# ACPowerDistributionUSB-PD.net
KiCad netlist of a schematic drawn in Altium Designer
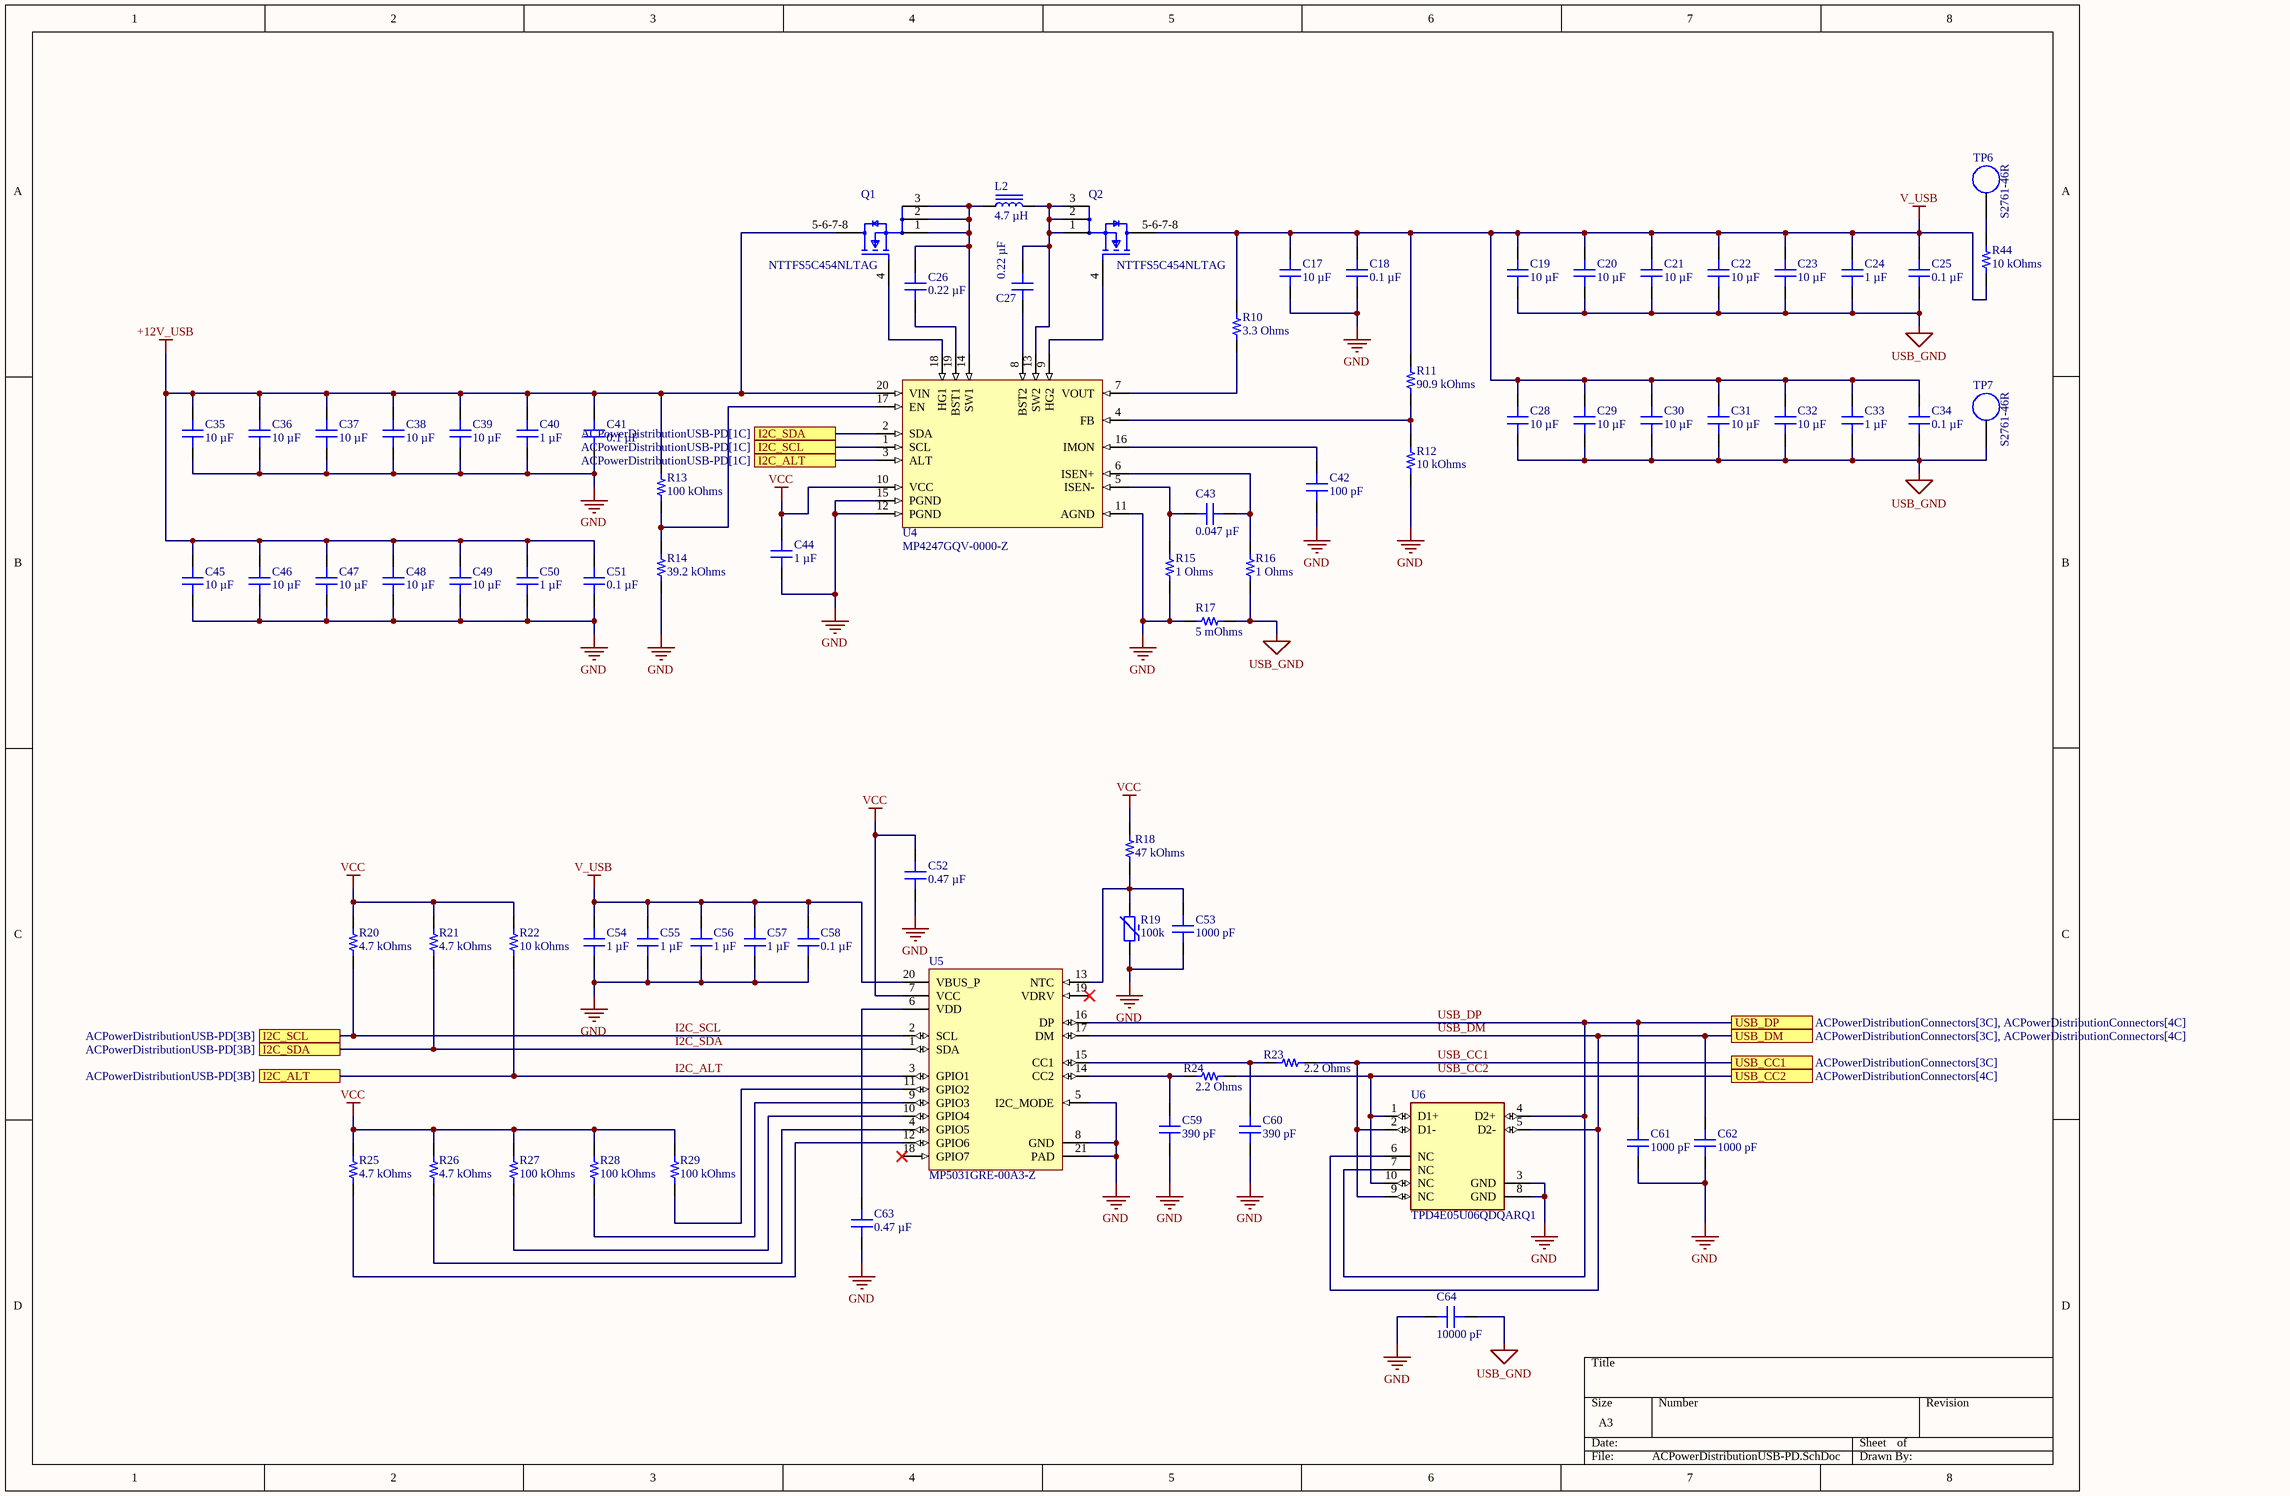
[diagram p0: ACPowerDistributionUSB-PD.SchDoc]

(export (version "E")
  (design (tool "Eeschema 10.0.6"))
  (components
    (comp (ref "C17")
      (value "10 µF")
      (footprint "CAP 1210_3225 - 1MM")
      (description "CAP CER 10UF 50V X7S 1210")
      (fields
        (field (name "PART NUMBER") "GCM32EC71H106KA03L")
        (field (name "MANUFACTURER") "Murata Electronics")
      )
      (libsource (lib "Celestial Altium Library - altium_library") (part "Capacitor"))
    )
    (comp (ref "C18")
      (value "0.1 µF")
      (footprint "CAP 0603_1608")
      (description "CAP CER 0.1UF 25V X7R 0603")
      (fields
        (field (name "PART NUMBER") "CL10B104KA8WPNC")
        (field (name "CAPACITANCE") "0.1 µF")
        (field (name "MANUFACTURER") "Samsung Electro-Mechanics")
      )
      (libsource (lib "Celestial Altium Library - altium_library") (part "Capacitor"))
    )
    (comp (ref "C19")
      (value "10 µF")
      (footprint "CAP 1210_3225 - 1MM")
      (description "CAP CER 10UF 50V X7S 1210")
      (fields
        (field (name "PART NUMBER") "GCM32EC71H106KA03L")
        (field (name "MANUFACTURER") "Murata Electronics")
      )
      (libsource (lib "Celestial Altium Library - altium_library") (part "Capacitor"))
    )
    (comp (ref "C20")
      (value "10 µF")
      (footprint "CAP 1210_3225 - 1MM")
      (description "CAP CER 10UF 50V X7S 1210")
      (fields
        (field (name "PART NUMBER") "GCM32EC71H106KA03L")
        (field (name "MANUFACTURER") "Murata Electronics")
      )
      (libsource (lib "Celestial Altium Library - altium_library") (part "Capacitor"))
    )
    (comp (ref "C21")
      (value "10 µF")
      (footprint "CAP 1210_3225 - 1MM")
      (description "CAP CER 10UF 50V X7S 1210")
      (fields
        (field (name "PART NUMBER") "GCM32EC71H106KA03L")
        (field (name "MANUFACTURER") "Murata Electronics")
      )
      (libsource (lib "Celestial Altium Library - altium_library") (part "Capacitor"))
    )
    (comp (ref "C22")
      (value "10 µF")
      (footprint "CAP 1210_3225 - 1MM")
      (description "CAP CER 10UF 50V X7S 1210")
      (fields
        (field (name "PART NUMBER") "GCM32EC71H106KA03L")
        (field (name "MANUFACTURER") "Murata Electronics")
      )
      (libsource (lib "Celestial Altium Library - altium_library") (part "Capacitor"))
    )
    (comp (ref "C23")
      (value "10 µF")
      (footprint "CAP 1210_3225 - 1MM")
      (description "CAP CER 10UF 50V X7S 1210")
      (fields
        (field (name "PART NUMBER") "GCM32EC71H106KA03L")
        (field (name "MANUFACTURER") "Murata Electronics")
      )
      (libsource (lib "Celestial Altium Library - altium_library") (part "Capacitor"))
    )
    (comp (ref "C24")
      (value "1 µF")
      (footprint "CAP 0603_1608")
      (description "CAP CER 1UF 25V X5R 0603")
      (fields
        (field (name "PART NUMBER") "CL10A105KA8NNNC")
        (field (name "CAPACITANCE") "1 µF")
        (field (name "MANUFACTURER") "Samsung Electro-Mechanics")
      )
      (libsource (lib "Celestial Altium Library - altium_library") (part "Capacitor"))
    )
    (comp (ref "C25")
      (value "0.1 µF")
      (footprint "CAP 0603_1608")
      (description "CAP CER 0.1UF 25V X7R 0603")
      (fields
        (field (name "PART NUMBER") "CL10B104KA8WPNC")
        (field (name "CAPACITANCE") "0.1 µF")
        (field (name "MANUFACTURER") "Samsung Electro-Mechanics")
      )
      (libsource (lib "Celestial Altium Library - altium_library") (part "Capacitor"))
    )
    (comp (ref "C26")
      (value "0.22 µF")
      (footprint "MURATA GRM188 0603_1608")
      (description "CAP CER 0.22UF 50V X7R 0603")
      (fields
        (field (name "PART NUMBER") "GRM188R71H224KAC4D")
        (field (name "CAPACITANCE") "0.22 µF")
        (field (name "MANUFACTURER") "Murata Electronics")
      )
      (libsource (lib "Celestial Altium Library - altium_library") (part "Capacitor"))
    )
    (comp (ref "C27")
      (value "0.22 µF")
      (footprint "MURATA GRM188 0603_1608")
      (description "CAP CER 0.22UF 50V X7R 0603")
      (fields
        (field (name "PART NUMBER") "GRM188R71H224KAC4D")
        (field (name "CAPACITANCE") "0.22 µF")
        (field (name "MANUFACTURER") "Murata Electronics")
      )
      (libsource (lib "Celestial Altium Library - altium_library") (part "Capacitor"))
    )
    (comp (ref "C28")
      (value "10 µF")
      (footprint "CAP 1210_3225 - 1MM")
      (description "CAP CER 10UF 50V X7S 1210")
      (fields
        (field (name "PART NUMBER") "GCM32EC71H106KA03L")
        (field (name "MANUFACTURER") "Murata Electronics")
      )
      (libsource (lib "Celestial Altium Library - altium_library") (part "Capacitor"))
    )
    (comp (ref "C29")
      (value "10 µF")
      (footprint "CAP 1210_3225 - 1MM")
      (description "CAP CER 10UF 50V X7S 1210")
      (fields
        (field (name "PART NUMBER") "GCM32EC71H106KA03L")
        (field (name "MANUFACTURER") "Murata Electronics")
      )
      (libsource (lib "Celestial Altium Library - altium_library") (part "Capacitor"))
    )
    (comp (ref "C30")
      (value "10 µF")
      (footprint "CAP 1210_3225 - 1MM")
      (description "CAP CER 10UF 50V X7S 1210")
      (fields
        (field (name "PART NUMBER") "GCM32EC71H106KA03L")
        (field (name "MANUFACTURER") "Murata Electronics")
      )
      (libsource (lib "Celestial Altium Library - altium_library") (part "Capacitor"))
    )
    (comp (ref "C31")
      (value "10 µF")
      (footprint "CAP 1210_3225 - 1MM")
      (description "CAP CER 10UF 50V X7S 1210")
      (fields
        (field (name "PART NUMBER") "GCM32EC71H106KA03L")
        (field (name "MANUFACTURER") "Murata Electronics")
      )
      (libsource (lib "Celestial Altium Library - altium_library") (part "Capacitor"))
    )
    (comp (ref "C32")
      (value "10 µF")
      (footprint "CAP 1210_3225 - 1MM")
      (description "CAP CER 10UF 50V X7S 1210")
      (fields
        (field (name "PART NUMBER") "GCM32EC71H106KA03L")
        (field (name "MANUFACTURER") "Murata Electronics")
      )
      (libsource (lib "Celestial Altium Library - altium_library") (part "Capacitor"))
    )
    (comp (ref "C33")
      (value "1 µF")
      (footprint "CAP 0603_1608")
      (description "CAP CER 1UF 25V X5R 0603")
      (fields
        (field (name "PART NUMBER") "CL10A105KA8NNNC")
        (field (name "CAPACITANCE") "1 µF")
        (field (name "MANUFACTURER") "Samsung Electro-Mechanics")
      )
      (libsource (lib "Celestial Altium Library - altium_library") (part "Capacitor"))
    )
    (comp (ref "C34")
      (value "0.1 µF")
      (footprint "CAP 0603_1608")
      (description "CAP CER 0.1UF 25V X7R 0603")
      (fields
        (field (name "PART NUMBER") "CL10B104KA8WPNC")
        (field (name "CAPACITANCE") "0.1 µF")
        (field (name "MANUFACTURER") "Samsung Electro-Mechanics")
      )
      (libsource (lib "Celestial Altium Library - altium_library") (part "Capacitor"))
    )
    (comp (ref "C35")
      (value "10 µF")
      (footprint "CAP 1210_3225 - 1MM")
      (description "CAP CER 10UF 50V X7S 1210")
      (fields
        (field (name "PART NUMBER") "GCM32EC71H106KA03L")
        (field (name "MANUFACTURER") "Murata Electronics")
      )
      (libsource (lib "Celestial Altium Library - altium_library") (part "Capacitor"))
    )
    (comp (ref "C36")
      (value "10 µF")
      (footprint "CAP 1210_3225 - 1MM")
      (description "CAP CER 10UF 50V X7S 1210")
      (fields
        (field (name "PART NUMBER") "GCM32EC71H106KA03L")
        (field (name "MANUFACTURER") "Murata Electronics")
      )
      (libsource (lib "Celestial Altium Library - altium_library") (part "Capacitor"))
    )
    (comp (ref "C37")
      (value "10 µF")
      (footprint "CAP 1210_3225 - 1MM")
      (description "CAP CER 10UF 50V X7S 1210")
      (fields
        (field (name "PART NUMBER") "GCM32EC71H106KA03L")
        (field (name "MANUFACTURER") "Murata Electronics")
      )
      (libsource (lib "Celestial Altium Library - altium_library") (part "Capacitor"))
    )
    (comp (ref "C38")
      (value "10 µF")
      (footprint "CAP 1210_3225 - 1MM")
      (description "CAP CER 10UF 50V X7S 1210")
      (fields
        (field (name "PART NUMBER") "GCM32EC71H106KA03L")
        (field (name "MANUFACTURER") "Murata Electronics")
      )
      (libsource (lib "Celestial Altium Library - altium_library") (part "Capacitor"))
    )
    (comp (ref "C39")
      (value "10 µF")
      (footprint "CAP 1210_3225 - 1MM")
      (description "CAP CER 10UF 50V X7S 1210")
      (fields
        (field (name "PART NUMBER") "GCM32EC71H106KA03L")
        (field (name "MANUFACTURER") "Murata Electronics")
      )
      (libsource (lib "Celestial Altium Library - altium_library") (part "Capacitor"))
    )
    (comp (ref "C40")
      (value "1 µF")
      (footprint "CAP 0603_1608")
      (description "CAP CER 1UF 25V X5R 0603")
      (fields
        (field (name "PART NUMBER") "CL10A105KA8NNNC")
        (field (name "CAPACITANCE") "1 µF")
        (field (name "MANUFACTURER") "Samsung Electro-Mechanics")
      )
      (libsource (lib "Celestial Altium Library - altium_library") (part "Capacitor"))
    )
    (comp (ref "C41")
      (value "0.1 µF")
      (footprint "CAP 0603_1608")
      (description "CAP CER 0.1UF 25V X7R 0603")
      (fields
        (field (name "PART NUMBER") "CL10B104KA8WPNC")
        (field (name "CAPACITANCE") "0.1 µF")
        (field (name "MANUFACTURER") "Samsung Electro-Mechanics")
      )
      (libsource (lib "Celestial Altium Library - altium_library") (part "Capacitor"))
    )
    (comp (ref "C42")
      (value "100 pF")
      (footprint "CAP 0603_1608")
      (description "CAP CER 100PF 25V C0G/NPO 0603")
      (fields
        (field (name "PART NUMBER") "CC0603JRNPO8BN101")
        (field (name "CAPACITANCE") "100 pF")
        (field (name "MANUFACTURER") "Yageo")
      )
      (libsource (lib "Celestial Altium Library - altium_library") (part "Capacitor"))
    )
    (comp (ref "C43")
      (value "0.047 µF")
      (footprint "CAP 0603_1608")
      (description "CAP CER 0.047UF 50V X7R 0603")
      (fields
        (field (name "PART NUMBER") "CL10B473KB8NNNC")
        (field (name "CAPACITANCE") "0.047 µF")
        (field (name "MANUFACTURER") "Samsung Electro-Mechanics")
      )
      (libsource (lib "Celestial Altium Library - altium_library") (part "Capacitor"))
    )
    (comp (ref "C44")
      (value "1 µF")
      (footprint "CAP 0603_1608")
      (description "CAP CER 1UF 25V X5R 0603")
      (fields
        (field (name "PART NUMBER") "CL10A105KA8NNNC")
        (field (name "CAPACITANCE") "1 µF")
        (field (name "MANUFACTURER") "Samsung Electro-Mechanics")
      )
      (libsource (lib "Celestial Altium Library - altium_library") (part "Capacitor"))
    )
    (comp (ref "C45")
      (value "10 µF")
      (footprint "CAP 1210_3225 - 1MM")
      (description "CAP CER 10UF 50V X7S 1210")
      (fields
        (field (name "PART NUMBER") "GCM32EC71H106KA03L")
        (field (name "MANUFACTURER") "Murata Electronics")
      )
      (libsource (lib "Celestial Altium Library - altium_library") (part "Capacitor"))
    )
    (comp (ref "C46")
      (value "10 µF")
      (footprint "CAP 1210_3225 - 1MM")
      (description "CAP CER 10UF 50V X7S 1210")
      (fields
        (field (name "PART NUMBER") "GCM32EC71H106KA03L")
        (field (name "MANUFACTURER") "Murata Electronics")
      )
      (libsource (lib "Celestial Altium Library - altium_library") (part "Capacitor"))
    )
    (comp (ref "C47")
      (value "10 µF")
      (footprint "CAP 1210_3225 - 1MM")
      (description "CAP CER 10UF 50V X7S 1210")
      (fields
        (field (name "PART NUMBER") "GCM32EC71H106KA03L")
        (field (name "MANUFACTURER") "Murata Electronics")
      )
      (libsource (lib "Celestial Altium Library - altium_library") (part "Capacitor"))
    )
    (comp (ref "C48")
      (value "10 µF")
      (footprint "CAP 1210_3225 - 1MM")
      (description "CAP CER 10UF 50V X7S 1210")
      (fields
        (field (name "PART NUMBER") "GCM32EC71H106KA03L")
        (field (name "MANUFACTURER") "Murata Electronics")
      )
      (libsource (lib "Celestial Altium Library - altium_library") (part "Capacitor"))
    )
    (comp (ref "C49")
      (value "10 µF")
      (footprint "CAP 1210_3225 - 1MM")
      (description "CAP CER 10UF 50V X7S 1210")
      (fields
        (field (name "PART NUMBER") "GCM32EC71H106KA03L")
        (field (name "MANUFACTURER") "Murata Electronics")
      )
      (libsource (lib "Celestial Altium Library - altium_library") (part "Capacitor"))
    )
    (comp (ref "C50")
      (value "1 µF")
      (footprint "CAP 0603_1608")
      (description "CAP CER 1UF 25V X5R 0603")
      (fields
        (field (name "PART NUMBER") "CL10A105KA8NNNC")
        (field (name "CAPACITANCE") "1 µF")
        (field (name "MANUFACTURER") "Samsung Electro-Mechanics")
      )
      (libsource (lib "Celestial Altium Library - altium_library") (part "Capacitor"))
    )
    (comp (ref "C51")
      (value "0.1 µF")
      (footprint "CAP 0603_1608")
      (description "CAP CER 0.1UF 25V X7R 0603")
      (fields
        (field (name "PART NUMBER") "CL10B104KA8WPNC")
        (field (name "CAPACITANCE") "0.1 µF")
        (field (name "MANUFACTURER") "Samsung Electro-Mechanics")
      )
      (libsource (lib "Celestial Altium Library - altium_library") (part "Capacitor"))
    )
    (comp (ref "C52")
      (value "0.47 µF")
      (footprint "CAP 0603_1608")
      (description "CAP CER 0.47UF 25V X5R 0603")
      (fields
        (field (name "PART NUMBER") "CC0603KRX5R8BB474")
        (field (name "CAPACITANCE") "0.47 µF")
        (field (name "MANUFACTURER") "Yageo")
      )
      (libsource (lib "Celestial Altium Library - altium_library") (part "Capacitor"))
    )
    (comp (ref "C53")
      (value "1000 pF")
      (footprint "CAP 0603_1608")
      (description "CAP CER 1000PF 16V C0G/NPO 0603")
      (fields
        (field (name "PART NUMBER") "CC0603JRNPO7BN102")
        (field (name "CAPACITANCE") "1000 pF")
        (field (name "MANUFACTURER") "Yageo")
      )
      (libsource (lib "Celestial Altium Library - altium_library") (part "Capacitor"))
    )
    (comp (ref "C54")
      (value "1 µF")
      (footprint "CAP 0603_1608")
      (description "CAP CER 1UF 25V X5R 0603")
      (fields
        (field (name "PART NUMBER") "CL10A105KA8NNNC")
        (field (name "CAPACITANCE") "1 µF")
        (field (name "MANUFACTURER") "Samsung Electro-Mechanics")
      )
      (libsource (lib "Celestial Altium Library - altium_library") (part "Capacitor"))
    )
    (comp (ref "C55")
      (value "1 µF")
      (footprint "CAP 0603_1608")
      (description "CAP CER 1UF 25V X5R 0603")
      (fields
        (field (name "PART NUMBER") "CL10A105KA8NNNC")
        (field (name "CAPACITANCE") "1 µF")
        (field (name "MANUFACTURER") "Samsung Electro-Mechanics")
      )
      (libsource (lib "Celestial Altium Library - altium_library") (part "Capacitor"))
    )
    (comp (ref "C56")
      (value "1 µF")
      (footprint "CAP 0603_1608")
      (description "CAP CER 1UF 25V X5R 0603")
      (fields
        (field (name "PART NUMBER") "CL10A105KA8NNNC")
        (field (name "CAPACITANCE") "1 µF")
        (field (name "MANUFACTURER") "Samsung Electro-Mechanics")
      )
      (libsource (lib "Celestial Altium Library - altium_library") (part "Capacitor"))
    )
    (comp (ref "C57")
      (value "1 µF")
      (footprint "CAP 0603_1608")
      (description "CAP CER 1UF 25V X5R 0603")
      (fields
        (field (name "PART NUMBER") "CL10A105KA8NNNC")
        (field (name "CAPACITANCE") "1 µF")
        (field (name "MANUFACTURER") "Samsung Electro-Mechanics")
      )
      (libsource (lib "Celestial Altium Library - altium_library") (part "Capacitor"))
    )
    (comp (ref "C58")
      (value "0.1 µF")
      (footprint "CAP 0603_1608")
      (description "CAP CER 0.1UF 25V X7R 0603")
      (fields
        (field (name "PART NUMBER") "CL10B104KA8WPNC")
        (field (name "CAPACITANCE") "0.1 µF")
        (field (name "MANUFACTURER") "Samsung Electro-Mechanics")
      )
      (libsource (lib "Celestial Altium Library - altium_library") (part "Capacitor"))
    )
    (comp (ref "C59")
      (value "390 pF")
      (footprint "CAP 0603_1608")
      (description "CAP CER 390PF 50V X7R 0603")
      (fields
        (field (name "PART NUMBER") "CC0603KRX7R9BB391")
        (field (name "CAPACITANCE") "390 pF")
        (field (name "MANUFACTURER") "Yageo")
      )
      (libsource (lib "Celestial Altium Library - altium_library") (part "Capacitor"))
    )
    (comp (ref "C60")
      (value "390 pF")
      (footprint "CAP 0603_1608")
      (description "CAP CER 390PF 50V X7R 0603")
      (fields
        (field (name "PART NUMBER") "CC0603KRX7R9BB391")
        (field (name "CAPACITANCE") "390 pF")
        (field (name "MANUFACTURER") "Yageo")
      )
      (libsource (lib "Celestial Altium Library - altium_library") (part "Capacitor"))
    )
    (comp (ref "C61")
      (value "1000 pF")
      (footprint "CAP 0603_1608")
      (description "CAP CER 1000PF 50V X8R 0603")
      (fields
        (field (name "PART NUMBER") "C1608X8R1H102K080AA")
        (field (name "CAPACITANCE") "1000 pF")
        (field (name "MANUFACTURER") "TDK Corporation")
      )
      (libsource (lib "Celestial Altium Library - altium_library") (part "Capacitor"))
    )
    (comp (ref "C62")
      (value "1000 pF")
      (footprint "CAP 0603_1608")
      (description "CAP CER 1000PF 50V X8R 0603")
      (fields
        (field (name "PART NUMBER") "C1608X8R1H102K080AA")
        (field (name "CAPACITANCE") "1000 pF")
        (field (name "MANUFACTURER") "TDK Corporation")
      )
      (libsource (lib "Celestial Altium Library - altium_library") (part "Capacitor"))
    )
    (comp (ref "C63")
      (value "0.47 µF")
      (footprint "CAP 0603_1608")
      (description "CAP CER 0.47UF 25V X5R 0603")
      (fields
        (field (name "PART NUMBER") "CC0603KRX5R8BB474")
        (field (name "CAPACITANCE") "0.47 µF")
        (field (name "MANUFACTURER") "Yageo")
      )
      (libsource (lib "Celestial Altium Library - altium_library") (part "Capacitor"))
    )
    (comp (ref "C64")
      (value "10000 pF")
      (footprint "CAP 0603_1608")
      (description "CAP CER 10000PF 50V X8R 0603")
      (fields
        (field (name "PART NUMBER") "CGA3E2X8R1H103K080AA")
        (field (name "CAPACITANCE") "10000 pF")
        (field (name "MANUFACTURER") "TDK Corporation")
      )
      (libsource (lib "Celestial Altium Library - altium_library") (part "Capacitor"))
    )
    (comp (ref "L2")
      (value "4.7 µH")
      (footprint "WURTH WE-HCI 7040")
      (description "FIXED IND 4.7UH 6A 19.5 MOHM SMD")
      (fields (field (name "PART NUMBER") "744311470") (field (name "MANUFACTURER") "Würth Elektronik"))
      (libsource (lib "Celestial Altium Library - altium_library") (part "Inductor"))
    )
    (comp (ref "Q1")
      (value "NTTFS5C454NLTAG")
      (footprint "FP-511AB-MFG")
      (libsource (lib "Altium Content Vault") (part "7382af88e928fdc71488234cfaaf11c"))
    )
    (comp (ref "Q2")
      (value "NTTFS5C454NLTAG")
      (footprint "FP-511AB-MFG")
      (libsource (lib "Altium Content Vault") (part "7382af88e928fdc71488234cfaaf11c"))
    )
    (comp (ref "R10")
      (value "3.3 Ohms")
      (footprint "RES 0603_1608")
      (description "RES 3.3 OHM 1% 1/10W 0603")
      (fields
        (field (name "PART NUMBER") "RMCF0603FT3R30")
        (field (name "MANUFACTURER") "Stackpole Electronics Inc")
      )
      (libsource (lib "Celestial Altium Library - altium_library") (part "Resistor"))
    )
    (comp (ref "R11")
      (value "90.9 kOhms")
      (footprint "RES 0603_1608")
      (description "RES 90.9K OHM 1% 1/10W 0603")
      (fields
        (field (name "PART NUMBER") "RMCF0603FT90K9")
        (field (name "MANUFACTURER") "Stackpole Electronics Inc")
      )
      (libsource (lib "Celestial Altium Library - altium_library") (part "Resistor"))
    )
    (comp (ref "R12")
      (value "10 kOhms")
      (footprint "RES 0603_1608")
      (description "RES 10K OHM 1% 1/10W 0603")
      (fields
        (field (name "PART NUMBER") "RMCF0603FT10K0")
        (field (name "MANUFACTURER") "Stackpole Electronics Inc")
      )
      (libsource (lib "Celestial Altium Library - altium_library") (part "Resistor"))
    )
    (comp (ref "R13")
      (value "100 kOhms")
      (footprint "RES 0603_1608")
      (description "RES 100K OHM 1% 1/10W 0603")
      (fields
        (field (name "PART NUMBER") "RMCF0603FT100K")
        (field (name "MANUFACTURER") "Stackpole Electronics Inc")
      )
      (libsource (lib "Celestial Altium Library - altium_library") (part "Resistor"))
    )
    (comp (ref "R14")
      (value "39.2 kOhms")
      (footprint "RES 0603_1608")
      (description "RES 39.2K OHM 1% 1/10W 0603")
      (fields
        (field (name "PART NUMBER") "RMCF0603FT39K2")
        (field (name "MANUFACTURER") "Stackpole Electronics Inc")
      )
      (libsource (lib "Celestial Altium Library - altium_library") (part "Resistor"))
    )
    (comp (ref "R15")
      (value "1 Ohms")
      (footprint "RES 0603_1608")
      (description "RES 1 OHM 1% 1/10W 0603")
      (fields
        (field (name "PART NUMBER") "RMCF0603FT1R00")
        (field (name "MANUFACTURER") "Stackpole Electronics Inc")
      )
      (libsource (lib "Celestial Altium Library - altium_library") (part "Resistor"))
    )
    (comp (ref "R16")
      (value "1 Ohms")
      (footprint "RES 0603_1608")
      (description "RES 1 OHM 1% 1/10W 0603")
      (fields
        (field (name "PART NUMBER") "RMCF0603FT1R00")
        (field (name "MANUFACTURER") "Stackpole Electronics Inc")
      )
      (libsource (lib "Celestial Altium Library - altium_library") (part "Resistor"))
    )
    (comp (ref "R17")
      (value "5 mOhms")
      (footprint "STACKPOLE CSR1206")
      (description "RES 0.005 OHM 1% 1W 1206")
      (fields (field (name "PART NUMBER") "CFN1206AFX-R005ELF") (field (name "MANUFACTURER") "Bourns Inc."))
      (libsource (lib "Celestial Altium Library - altium_library") (part "Resistor"))
    )
    (comp (ref "R18")
      (value "47 kOhms")
      (footprint "RES 0603_1608")
      (description "RES 47K OHM 1% 1/10W 0603")
      (fields
        (field (name "PART NUMBER") "RMCF0603FT47K0")
        (field (name "MANUFACTURER") "Stackpole Electronics Inc")
      )
      (libsource (lib "Celestial Altium Library - altium_library") (part "Resistor"))
    )
    (comp (ref "R19")
      (value "100k")
      (footprint "NTC 0603_1608")
      (description "THERM NTC 100KOHM 4200K 0603")
      (fields (field (name "PART NUMBER") "B57355V5104F360") (field (name "MANUFACTURER") "EPCOS (TDK)"))
      (libsource (lib "Celestial Altium Library - altium_library") (part "Thermistor"))
    )
    (comp (ref "R20")
      (value "4.7 kOhms")
      (footprint "RES 0603_1608")
      (description "RES 4.7K OHM 1% 1/10W 0603")
      (fields
        (field (name "PART NUMBER") "RMCF0603FT4K70")
        (field (name "MANUFACTURER") "Stackpole Electronics Inc")
      )
      (libsource (lib "Celestial Altium Library - altium_library") (part "Resistor"))
    )
    (comp (ref "R21")
      (value "4.7 kOhms")
      (footprint "RES 0603_1608")
      (description "RES 4.7K OHM 1% 1/10W 0603")
      (fields
        (field (name "PART NUMBER") "RMCF0603FT4K70")
        (field (name "MANUFACTURER") "Stackpole Electronics Inc")
      )
      (libsource (lib "Celestial Altium Library - altium_library") (part "Resistor"))
    )
    (comp (ref "R22")
      (value "10 kOhms")
      (footprint "RES 0603_1608")
      (description "RES 10K OHM 1% 1/10W 0603")
      (fields
        (field (name "PART NUMBER") "RMCF0603FT10K0")
        (field (name "MANUFACTURER") "Stackpole Electronics Inc")
      )
      (libsource (lib "Celestial Altium Library - altium_library") (part "Resistor"))
    )
    (comp (ref "R23")
      (value "2.2 Ohms")
      (footprint "RES 0603_1608")
      (description "RES 2.2 OHM 1% 1/10W 0603")
      (fields
        (field (name "PART NUMBER") "RMCF0603FT2R20")
        (field (name "MANUFACTURER") "Stackpole Electronics Inc")
      )
      (libsource (lib "Celestial Altium Library - altium_library") (part "Resistor"))
    )
    (comp (ref "R24")
      (value "2.2 Ohms")
      (footprint "RES 0603_1608")
      (description "RES 2.2 OHM 1% 1/10W 0603")
      (fields
        (field (name "PART NUMBER") "RMCF0603FT2R20")
        (field (name "MANUFACTURER") "Stackpole Electronics Inc")
      )
      (libsource (lib "Celestial Altium Library - altium_library") (part "Resistor"))
    )
    (comp (ref "R25")
      (value "4.7 kOhms")
      (footprint "RES 0603_1608")
      (description "RES 4.7K OHM 1% 1/10W 0603")
      (fields
        (field (name "PART NUMBER") "RMCF0603FT4K70")
        (field (name "MANUFACTURER") "Stackpole Electronics Inc")
      )
      (libsource (lib "Celestial Altium Library - altium_library") (part "Resistor"))
    )
    (comp (ref "R26")
      (value "4.7 kOhms")
      (footprint "RES 0603_1608")
      (description "RES 4.7K OHM 1% 1/10W 0603")
      (fields
        (field (name "PART NUMBER") "RMCF0603FT4K70")
        (field (name "MANUFACTURER") "Stackpole Electronics Inc")
      )
      (libsource (lib "Celestial Altium Library - altium_library") (part "Resistor"))
    )
    (comp (ref "R27")
      (value "100 kOhms")
      (footprint "RES 0603_1608")
      (description "RES 100K OHM 1% 1/10W 0603")
      (fields
        (field (name "PART NUMBER") "RMCF0603FT100K")
        (field (name "MANUFACTURER") "Stackpole Electronics Inc")
      )
      (libsource (lib "Celestial Altium Library - altium_library") (part "Resistor"))
    )
    (comp (ref "R28")
      (value "100 kOhms")
      (footprint "RES 0603_1608")
      (description "RES 100K OHM 1% 1/10W 0603")
      (fields
        (field (name "PART NUMBER") "RMCF0603FT100K")
        (field (name "MANUFACTURER") "Stackpole Electronics Inc")
      )
      (libsource (lib "Celestial Altium Library - altium_library") (part "Resistor"))
    )
    (comp (ref "R29")
      (value "100 kOhms")
      (footprint "RES 0603_1608")
      (description "RES 100K OHM 1% 1/10W 0603")
      (fields
        (field (name "PART NUMBER") "RMCF0603FT100K")
        (field (name "MANUFACTURER") "Stackpole Electronics Inc")
      )
      (libsource (lib "Celestial Altium Library - altium_library") (part "Resistor"))
    )
    (comp (ref "R44")
      (value "10 kOhms")
      (footprint "RES 0603_1608")
      (description "RES 10K OHM 1% 1/10W 0603")
      (fields
        (field (name "PART NUMBER") "RMCF0603FT10K0")
        (field (name "MANUFACTURER") "Stackpole Electronics Inc")
      )
      (libsource (lib "Celestial Altium Library - altium_library") (part "Resistor"))
    )
    (comp (ref "TP6")
      (value "S2761-46R")
      (footprint "S2761-46R")
      (libsource (lib "PersonalLibrary") (part "S2761-46R"))
    )
    (comp (ref "TP7")
      (value "S2761-46R")
      (footprint "S2761-46R")
      (libsource (lib "PersonalLibrary") (part "S2761-46R"))
    )
    (comp (ref "U4")
      (value "MP4247GQV-0000-Z")
      (footprint "MP4247GQV")
      (libsource (lib "PersonalLibrary") (part "MP4247GQV-0000-Z"))
    )
    (comp (ref "U5")
      (value "MP5031GRE-00A3-Z")
      (footprint "MP5031GRE")
      (libsource (lib "PersonalLibrary") (part "MP5031GRE-00A3-Z"))
    )
    (comp (ref "U6")
      (value "TPD4E05U06QDQARQ1")
      (footprint "FP-DQA0010A-MFG")
      (description "TVS DIODE 5.5V 14V 10USON")
      (fields
        (field (name "OCTOPART") "https://octopart.com/tpd4e05u06qdqarq1-texas+instruments-48523459")
        (field (name "MANUFACTURER") "Texas Instruments")
      )
      (libsource (lib "Altium Content Vault") (part "f11f7ff102fa2b028e1355c732c836d"))
    )
  )
  (nets
    (net (code "1") (name "+12V_USB") (class "Default")
      (node (ref "C35") (pin "2") (pinfunction "2_2") (pintype "passive"))
      (node (ref "C36") (pin "2") (pinfunction "2_2") (pintype "passive"))
      (node (ref "C37") (pin "2") (pinfunction "2_2") (pintype "passive"))
      (node (ref "C38") (pin "2") (pinfunction "2_2") (pintype "passive"))
      (node (ref "C39") (pin "2") (pinfunction "2_2") (pintype "passive"))
      (node (ref "C40") (pin "2") (pinfunction "2_2") (pintype "passive"))
      (node (ref "C41") (pin "2") (pinfunction "2_2") (pintype "passive"))
      (node (ref "C45") (pin "2") (pinfunction "2_2") (pintype "passive"))
      (node (ref "C46") (pin "2") (pinfunction "2_2") (pintype "passive"))
      (node (ref "C47") (pin "2") (pinfunction "2_2") (pintype "passive"))
      (node (ref "C48") (pin "2") (pinfunction "2_2") (pintype "passive"))
      (node (ref "C49") (pin "2") (pinfunction "2_2") (pintype "passive"))
      (node (ref "C50") (pin "2") (pinfunction "2_2") (pintype "passive"))
      (node (ref "C51") (pin "2") (pinfunction "2_2") (pintype "passive"))
      (node (ref "Q1") (pin "5-6-7-8") (pinfunction "D_5-6-7-8") (pintype "passive"))
      (node (ref "R13") (pin "2") (pinfunction "2_2") (pintype "passive"))
      (node (ref "U4") (pin "20") (pinfunction "VIN_20") (pintype "input"))
    )
    (net (code "2") (name "/I2C_ALT") (class "Default")
      (node (ref "R22") (pin "1") (pinfunction "1_1") (pintype "passive"))
      (node (ref "U4") (pin "3") (pinfunction "ALT_3") (pintype "input"))
      (node (ref "U5") (pin "3") (pinfunction "GPIO1_3") (pintype "bidirectional"))
    )
    (net (code "3") (name "/I2C_SCL") (class "Default")
      (node (ref "R20") (pin "1") (pinfunction "1_1") (pintype "passive"))
      (node (ref "U4") (pin "1") (pinfunction "SCL_1") (pintype "input"))
      (node (ref "U5") (pin "2") (pinfunction "SCL_2") (pintype "bidirectional"))
    )
    (net (code "4") (name "/I2C_SDA") (class "Default")
      (node (ref "R21") (pin "1") (pinfunction "1_1") (pintype "passive"))
      (node (ref "U4") (pin "2") (pinfunction "SDA_2") (pintype "input"))
      (node (ref "U5") (pin "1") (pinfunction "SDA_1") (pintype "bidirectional"))
    )
    (net (code "5") (name "/USB_CC1") (class "Default")
      (node (ref "R23") (pin "2") (pinfunction "2_2") (pintype "passive"))
      (node (ref "U6") (pin "2") (pinfunction "D1-_2") (pintype "bidirectional"))
      (node (ref "U6") (pin "9") (pinfunction "NC_9") (pintype "bidirectional"))
    )
    (net (code "6") (name "/USB_CC2") (class "Default")
      (node (ref "R24") (pin "2") (pinfunction "2_2") (pintype "passive"))
      (node (ref "U6") (pin "1") (pinfunction "D1+_1") (pintype "bidirectional"))
      (node (ref "U6") (pin "10") (pinfunction "NC_10") (pintype "bidirectional"))
    )
    (net (code "7") (name "/USB_DM") (class "Default")
      (node (ref "C62") (pin "2") (pinfunction "2_2") (pintype "passive"))
      (node (ref "U5") (pin "17") (pinfunction "DM_17") (pintype "bidirectional"))
      (node (ref "U6") (pin "5") (pinfunction "D2-_5") (pintype "bidirectional"))
      (node (ref "U6") (pin "6") (pinfunction "NC_6") (pintype "passive"))
    )
    (net (code "8") (name "/USB_DP") (class "Default")
      (node (ref "C61") (pin "2") (pinfunction "2_2") (pintype "passive"))
      (node (ref "U5") (pin "16") (pinfunction "DP_16") (pintype "bidirectional"))
      (node (ref "U6") (pin "4") (pinfunction "D2+_4") (pintype "bidirectional"))
      (node (ref "U6") (pin "7") (pinfunction "NC_7") (pintype "passive"))
    )
    (net (code "9") (name "GND") (class "Default")
      (node (ref "C17") (pin "1") (pinfunction "1_1") (pintype "passive"))
      (node (ref "C18") (pin "1") (pinfunction "1_1") (pintype "passive"))
      (node (ref "C35") (pin "1") (pinfunction "1_1") (pintype "passive"))
      (node (ref "C36") (pin "1") (pinfunction "1_1") (pintype "passive"))
      (node (ref "C37") (pin "1") (pinfunction "1_1") (pintype "passive"))
      (node (ref "C38") (pin "1") (pinfunction "1_1") (pintype "passive"))
      (node (ref "C39") (pin "1") (pinfunction "1_1") (pintype "passive"))
      (node (ref "C40") (pin "1") (pinfunction "1_1") (pintype "passive"))
      (node (ref "C41") (pin "1") (pinfunction "1_1") (pintype "passive"))
      (node (ref "C42") (pin "1") (pinfunction "1_1") (pintype "passive"))
      (node (ref "C44") (pin "1") (pinfunction "1_1") (pintype "passive"))
      (node (ref "C45") (pin "1") (pinfunction "1_1") (pintype "passive"))
      (node (ref "C46") (pin "1") (pinfunction "1_1") (pintype "passive"))
      (node (ref "C47") (pin "1") (pinfunction "1_1") (pintype "passive"))
      (node (ref "C48") (pin "1") (pinfunction "1_1") (pintype "passive"))
      (node (ref "C49") (pin "1") (pinfunction "1_1") (pintype "passive"))
      (node (ref "C50") (pin "1") (pinfunction "1_1") (pintype "passive"))
      (node (ref "C51") (pin "1") (pinfunction "1_1") (pintype "passive"))
      (node (ref "C52") (pin "1") (pinfunction "1_1") (pintype "passive"))
      (node (ref "C53") (pin "1") (pinfunction "1_1") (pintype "passive"))
      (node (ref "C54") (pin "1") (pinfunction "1_1") (pintype "passive"))
      (node (ref "C55") (pin "1") (pinfunction "1_1") (pintype "passive"))
      (node (ref "C56") (pin "1") (pinfunction "1_1") (pintype "passive"))
      (node (ref "C57") (pin "1") (pinfunction "1_1") (pintype "passive"))
      (node (ref "C58") (pin "1") (pinfunction "1_1") (pintype "passive"))
      (node (ref "C59") (pin "1") (pinfunction "1_1") (pintype "passive"))
      (node (ref "C60") (pin "1") (pinfunction "1_1") (pintype "passive"))
      (node (ref "C61") (pin "1") (pinfunction "1_1") (pintype "passive"))
      (node (ref "C62") (pin "1") (pinfunction "1_1") (pintype "passive"))
      (node (ref "C63") (pin "1") (pinfunction "1_1") (pintype "passive"))
      (node (ref "C64") (pin "1") (pinfunction "1_1") (pintype "passive"))
      (node (ref "R12") (pin "1") (pinfunction "1_1") (pintype "passive"))
      (node (ref "R14") (pin "1") (pinfunction "1_1") (pintype "passive"))
      (node (ref "R15") (pin "1") (pinfunction "1_1") (pintype "passive"))
      (node (ref "R17") (pin "1") (pinfunction "1_1") (pintype "passive"))
      (node (ref "R19") (pin "1") (pinfunction "1_1") (pintype "passive"))
      (node (ref "U4") (pin "11") (pinfunction "AGND_11") (pintype "input"))
      (node (ref "U4") (pin "12") (pinfunction "PGND_12") (pintype "input"))
      (node (ref "U4") (pin "15") (pinfunction "PGND_15") (pintype "input"))
      (node (ref "U5") (pin "21") (pinfunction "PAD_21") (pintype "power_in"))
      (node (ref "U5") (pin "5") (pinfunction "I2C_MODE_5") (pintype "input"))
      (node (ref "U5") (pin "8") (pinfunction "GND_8") (pintype "power_in"))
      (node (ref "U6") (pin "3") (pinfunction "GND_3") (pintype "power_in"))
      (node (ref "U6") (pin "8") (pinfunction "GND_8") (pintype "power_in"))
    )
    (net (code "10") (name "Net-(Q1-G)") (class "Default")
      (node (ref "Q1") (pin "4") (pinfunction "G_4") (pintype "passive"))
      (node (ref "U4") (pin "18") (pinfunction "HG1_18") (pintype "input"))
    )
    (net (code "11") (name "Net-(Q2-G)") (class "Default")
      (node (ref "Q2") (pin "4") (pinfunction "G_4") (pintype "passive"))
      (node (ref "U4") (pin "9") (pinfunction "HG2_9") (pintype "input"))
    )
    (net (code "12") (name "Net-(R44-Pad2)") (class "Default")
      (node (ref "R44") (pin "2") (pinfunction "2_2") (pintype "passive"))
      (node (ref "TP6") (pin "1") (pinfunction "1_1") (pintype "passive"))
    )
    (net (code "13") (name "Net-(U4-BST1)") (class "Default")
      (node (ref "C26") (pin "1") (pinfunction "1_1") (pintype "passive"))
      (node (ref "U4") (pin "19") (pinfunction "BST1_19") (pintype "input"))
    )
    (net (code "14") (name "Net-(U4-BST2)") (class "Default")
      (node (ref "C27") (pin "1") (pinfunction "1_1") (pintype "passive"))
      (node (ref "U4") (pin "8") (pinfunction "BST2_8") (pintype "input"))
    )
    (net (code "15") (name "Net-(U4-EN)") (class "Default")
      (node (ref "R13") (pin "1") (pinfunction "1_1") (pintype "passive"))
      (node (ref "R14") (pin "2") (pinfunction "2_2") (pintype "passive"))
      (node (ref "U4") (pin "17") (pinfunction "EN_17") (pintype "input"))
    )
    (net (code "16") (name "Net-(U4-FB)") (class "Default")
      (node (ref "R11") (pin "1") (pinfunction "1_1") (pintype "passive"))
      (node (ref "R12") (pin "2") (pinfunction "2_2") (pintype "passive"))
      (node (ref "U4") (pin "4") (pinfunction "FB_4") (pintype "input"))
    )
    (net (code "17") (name "Net-(U4-IMON)") (class "Default")
      (node (ref "C42") (pin "2") (pinfunction "2_2") (pintype "passive"))
      (node (ref "U4") (pin "16") (pinfunction "IMON_16") (pintype "input"))
    )
    (net (code "18") (name "Net-(U4-ISEN+)") (class "Default")
      (node (ref "C43") (pin "2") (pinfunction "2_2") (pintype "passive"))
      (node (ref "R16") (pin "2") (pinfunction "2_2") (pintype "passive"))
      (node (ref "U4") (pin "6") (pinfunction "ISEN+_6") (pintype "input"))
    )
    (net (code "19") (name "Net-(U4-ISEN-)") (class "Default")
      (node (ref "C43") (pin "1") (pinfunction "1_1") (pintype "passive"))
      (node (ref "R15") (pin "2") (pinfunction "2_2") (pintype "passive"))
      (node (ref "U4") (pin "5") (pinfunction "ISEN-_5") (pintype "input"))
    )
    (net (code "20") (name "Net-(U4-SW1)") (class "Default")
      (node (ref "C26") (pin "2") (pinfunction "2_2") (pintype "passive"))
      (node (ref "L2") (pin "1") (pinfunction "1_1") (pintype "passive"))
      (node (ref "Q1") (pin "1") (pinfunction "S_1") (pintype "passive"))
      (node (ref "Q1") (pin "2") (pinfunction "S_2") (pintype "passive"))
      (node (ref "Q1") (pin "3") (pinfunction "S_3") (pintype "passive"))
      (node (ref "U4") (pin "14") (pinfunction "SW1_14") (pintype "input"))
    )
    (net (code "21") (name "Net-(U4-SW2)") (class "Default")
      (node (ref "C27") (pin "2") (pinfunction "2_2") (pintype "passive"))
      (node (ref "L2") (pin "2") (pinfunction "2_2") (pintype "passive"))
      (node (ref "Q2") (pin "1") (pinfunction "S_1") (pintype "passive"))
      (node (ref "Q2") (pin "2") (pinfunction "S_2") (pintype "passive"))
      (node (ref "Q2") (pin "3") (pinfunction "S_3") (pintype "passive"))
      (node (ref "U4") (pin "13") (pinfunction "SW2_13") (pintype "input"))
    )
    (net (code "22") (name "Net-(U4-VOUT)") (class "Default")
      (node (ref "R10") (pin "1") (pinfunction "1_1") (pintype "passive"))
      (node (ref "U4") (pin "7") (pinfunction "VOUT_7") (pintype "input"))
    )
    (net (code "23") (name "Net-(U5-CC1)") (class "Default")
      (node (ref "C60") (pin "2") (pinfunction "2_2") (pintype "passive"))
      (node (ref "R23") (pin "1") (pinfunction "1_1") (pintype "passive"))
      (node (ref "U5") (pin "15") (pinfunction "CC1_15") (pintype "bidirectional"))
    )
    (net (code "24") (name "Net-(U5-CC2)") (class "Default")
      (node (ref "C59") (pin "2") (pinfunction "2_2") (pintype "passive"))
      (node (ref "R24") (pin "1") (pinfunction "1_1") (pintype "passive"))
      (node (ref "U5") (pin "14") (pinfunction "CC2_14") (pintype "bidirectional"))
    )
    (net (code "25") (name "Net-(U5-GPIO2)") (class "Default")
      (node (ref "R29") (pin "1") (pinfunction "1_1") (pintype "passive"))
      (node (ref "U5") (pin "11") (pinfunction "GPIO2_11") (pintype "bidirectional"))
    )
    (net (code "26") (name "Net-(U5-GPIO3)") (class "Default")
      (node (ref "R28") (pin "1") (pinfunction "1_1") (pintype "passive"))
      (node (ref "U5") (pin "9") (pinfunction "GPIO3_9") (pintype "bidirectional"))
    )
    (net (code "27") (name "Net-(U5-GPIO4)") (class "Default")
      (node (ref "R27") (pin "1") (pinfunction "1_1") (pintype "passive"))
      (node (ref "U5") (pin "10") (pinfunction "GPIO4_10") (pintype "bidirectional"))
    )
    (net (code "28") (name "Net-(U5-GPIO5)") (class "Default")
      (node (ref "R26") (pin "1") (pinfunction "1_1") (pintype "passive"))
      (node (ref "U5") (pin "4") (pinfunction "GPIO5_4") (pintype "bidirectional"))
    )
    (net (code "29") (name "Net-(U5-GPIO6)") (class "Default")
      (node (ref "R25") (pin "1") (pinfunction "1_1") (pintype "passive"))
      (node (ref "U5") (pin "12") (pinfunction "GPIO6_12") (pintype "bidirectional"))
    )
    (net (code "30") (name "Net-(U5-NTC)") (class "Default")
      (node (ref "C53") (pin "2") (pinfunction "2_2") (pintype "passive"))
      (node (ref "R18") (pin "1") (pinfunction "1_1") (pintype "passive"))
      (node (ref "R19") (pin "2") (pinfunction "2_2") (pintype "passive"))
      (node (ref "U5") (pin "13") (pinfunction "NTC_13") (pintype "input"))
    )
    (net (code "31") (name "Net-(U5-VDD)") (class "Default")
      (node (ref "C63") (pin "2") (pinfunction "2_2") (pintype "passive"))
      (node (ref "U5") (pin "6") (pinfunction "VDD_6") (pintype "power_in"))
    )
    (net (code "32") (name "USB_GND") (class "Default")
      (node (ref "C19") (pin "1") (pinfunction "1_1") (pintype "passive"))
      (node (ref "C20") (pin "1") (pinfunction "1_1") (pintype "passive"))
      (node (ref "C21") (pin "1") (pinfunction "1_1") (pintype "passive"))
      (node (ref "C22") (pin "1") (pinfunction "1_1") (pintype "passive"))
      (node (ref "C23") (pin "1") (pinfunction "1_1") (pintype "passive"))
      (node (ref "C24") (pin "1") (pinfunction "1_1") (pintype "passive"))
      (node (ref "C25") (pin "1") (pinfunction "1_1") (pintype "passive"))
      (node (ref "C28") (pin "1") (pinfunction "1_1") (pintype "passive"))
      (node (ref "C29") (pin "1") (pinfunction "1_1") (pintype "passive"))
      (node (ref "C30") (pin "1") (pinfunction "1_1") (pintype "passive"))
      (node (ref "C31") (pin "1") (pinfunction "1_1") (pintype "passive"))
      (node (ref "C32") (pin "1") (pinfunction "1_1") (pintype "passive"))
      (node (ref "C33") (pin "1") (pinfunction "1_1") (pintype "passive"))
      (node (ref "C34") (pin "1") (pinfunction "1_1") (pintype "passive"))
      (node (ref "C64") (pin "2") (pinfunction "2_2") (pintype "passive"))
      (node (ref "R16") (pin "1") (pinfunction "1_1") (pintype "passive"))
      (node (ref "R17") (pin "2") (pinfunction "2_2") (pintype "passive"))
      (node (ref "TP7") (pin "1") (pinfunction "1_1") (pintype "passive"))
    )
    (net (code "33") (name "VCC") (class "Default")
      (node (ref "C44") (pin "2") (pinfunction "2_2") (pintype "passive"))
      (node (ref "C52") (pin "2") (pinfunction "2_2") (pintype "passive"))
      (node (ref "R18") (pin "2") (pinfunction "2_2") (pintype "passive"))
      (node (ref "R20") (pin "2") (pinfunction "2_2") (pintype "passive"))
      (node (ref "R21") (pin "2") (pinfunction "2_2") (pintype "passive"))
      (node (ref "R22") (pin "2") (pinfunction "2_2") (pintype "passive"))
      (node (ref "R25") (pin "2") (pinfunction "2_2") (pintype "passive"))
      (node (ref "R26") (pin "2") (pinfunction "2_2") (pintype "passive"))
      (node (ref "R27") (pin "2") (pinfunction "2_2") (pintype "passive"))
      (node (ref "R28") (pin "2") (pinfunction "2_2") (pintype "passive"))
      (node (ref "R29") (pin "2") (pinfunction "2_2") (pintype "passive"))
      (node (ref "U4") (pin "10") (pinfunction "VCC_10") (pintype "input"))
      (node (ref "U5") (pin "7") (pinfunction "VCC_7") (pintype "power_in"))
    )
    (net (code "34") (name "V_USB") (class "Default")
      (node (ref "C17") (pin "2") (pinfunction "2_2") (pintype "passive"))
      (node (ref "C18") (pin "2") (pinfunction "2_2") (pintype "passive"))
      (node (ref "C19") (pin "2") (pinfunction "2_2") (pintype "passive"))
      (node (ref "C20") (pin "2") (pinfunction "2_2") (pintype "passive"))
      (node (ref "C21") (pin "2") (pinfunction "2_2") (pintype "passive"))
      (node (ref "C22") (pin "2") (pinfunction "2_2") (pintype "passive"))
      (node (ref "C23") (pin "2") (pinfunction "2_2") (pintype "passive"))
      (node (ref "C24") (pin "2") (pinfunction "2_2") (pintype "passive"))
      (node (ref "C25") (pin "2") (pinfunction "2_2") (pintype "passive"))
      (node (ref "C28") (pin "2") (pinfunction "2_2") (pintype "passive"))
      (node (ref "C29") (pin "2") (pinfunction "2_2") (pintype "passive"))
      (node (ref "C30") (pin "2") (pinfunction "2_2") (pintype "passive"))
      (node (ref "C31") (pin "2") (pinfunction "2_2") (pintype "passive"))
      (node (ref "C32") (pin "2") (pinfunction "2_2") (pintype "passive"))
      (node (ref "C33") (pin "2") (pinfunction "2_2") (pintype "passive"))
      (node (ref "C34") (pin "2") (pinfunction "2_2") (pintype "passive"))
      (node (ref "C54") (pin "2") (pinfunction "2_2") (pintype "passive"))
      (node (ref "C55") (pin "2") (pinfunction "2_2") (pintype "passive"))
      (node (ref "C56") (pin "2") (pinfunction "2_2") (pintype "passive"))
      (node (ref "C57") (pin "2") (pinfunction "2_2") (pintype "passive"))
      (node (ref "C58") (pin "2") (pinfunction "2_2") (pintype "passive"))
      (node (ref "Q2") (pin "5-6-7-8") (pinfunction "D_5-6-7-8") (pintype "passive"))
      (node (ref "R10") (pin "2") (pinfunction "2_2") (pintype "passive"))
      (node (ref "R11") (pin "2") (pinfunction "2_2") (pintype "passive"))
      (node (ref "R44") (pin "1") (pinfunction "1_1") (pintype "passive"))
      (node (ref "U5") (pin "20") (pinfunction "VBUS_P_20") (pintype "power_in"))
    )
    (net (code "35") (name "unconnected-(U5-GPIO7-Pad18)") (class "Default")
      (node (ref "U5") (pin "18") (pinfunction "GPIO7_18") (pintype "input+no_connect"))
    )
    (net (code "36") (name "unconnected-(U5-VDRV-Pad19)") (class "Default")
      (node (ref "U5") (pin "19") (pinfunction "VDRV_19") (pintype "input+no_connect"))
    )
  )
)
